# motor-board.net
KiCad netlist of a schematic drawn in EAGLE
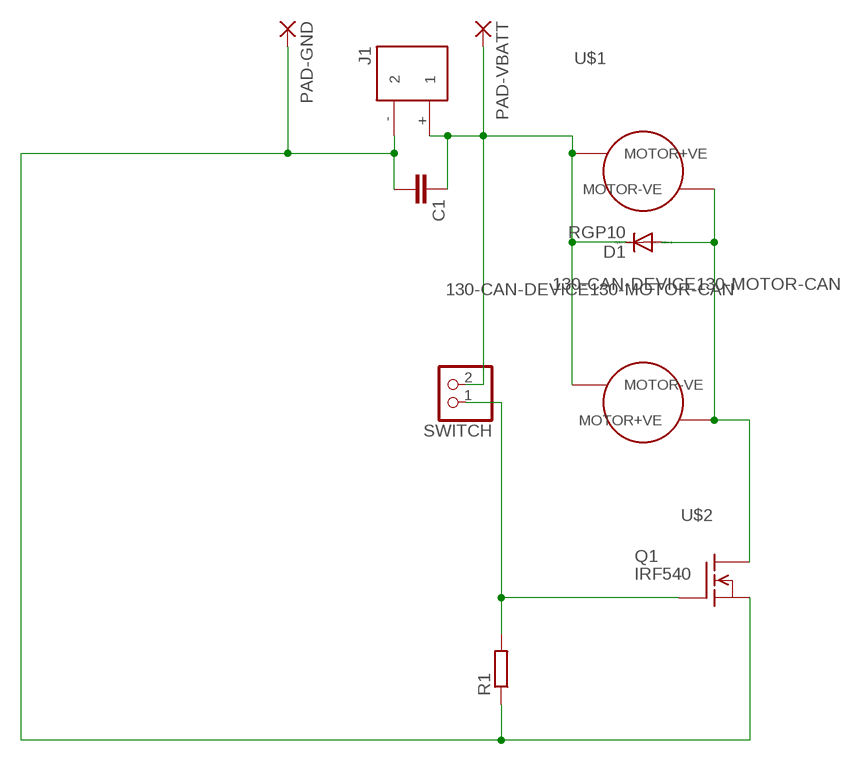
[diagram p0: schematic, sheet 1]

(export (version "E")
  (design (tool "Eeschema 10.0.6"))
  (components
    (comp (ref "C1")
      (value "C-EU050-024X044")
      (footprint "eagle-import:C050-024X044")
      (libsource (lib "eagle-import") (part "C-EU050-024X044"))
    )
    (comp (ref "D1")
      (value "RGP10")
      (footprint "eagle-import:DO41-10")
      (libsource (lib "eagle-import") (part "RGP10"))
    )
    (comp (ref "J1")
      (value "XT60_FEMALE")
      (footprint "eagle-import:XT60_FEMALE")
      (libsource (lib "eagle-import") (part "XT60_FEMALE"))
    )
    (comp (ref "PAD-GND")
      (value "WIREPAD3,81/1,4")
      (footprint "eagle-import:3,81_1,4")
      (libsource (lib "eagle-import") (part "WIREPAD3,81/1,4"))
    )
    (comp (ref "PAD-VBATT")
      (value "WIREPAD3,81/1,4")
      (footprint "eagle-import:3,81_1,4")
      (libsource (lib "eagle-import") (part "WIREPAD3,81/1,4"))
    )
    (comp (ref "Q1")
      (value "IRF540")
      (footprint "eagle-import:TO220")
      (libsource (lib "eagle-import") (part "IRF540"))
    )
    (comp (ref "R1")
      (value "R-EU_0309/10")
      (footprint "eagle-import:0309_10")
      (libsource (lib "eagle-import") (part "R-EU_0309/10"))
    )
    (comp (ref "SWITCH")
      (value "PINHD-1X2")
      (footprint "eagle-import:1X02")
      (libsource (lib "eagle-import") (part "PINHD-1X2"))
    )
    (comp (ref "U$1")
      (value "130-CAN-DEVICE130-MOTOR-CAN")
      (footprint "eagle-import:130-MOTOR-CAN")
      (libsource (lib "eagle-import") (part "130-CAN-DEVICE130-MOTOR-CAN"))
    )
    (comp (ref "U$2")
      (value "130-CAN-DEVICE130-MOTOR-CAN")
      (footprint "eagle-import:130-MOTOR-CAN")
      (libsource (lib "eagle-import") (part "130-CAN-DEVICE130-MOTOR-CAN"))
    )
  )
  (nets
    (net (code "1") (name "Net-(J1-1)") (class "Default")
      (node (ref "C1") (pin "1") (pinfunction "1_1") (pintype "passive"))
      (node (ref "D1") (pin "C") (pinfunction "C_C") (pintype "passive"))
      (node (ref "J1") (pin "+") (pinfunction "1_+") (pintype "bidirectional"))
      (node (ref "PAD-VBATT") (pin "1") (pinfunction "P_1") (pintype "passive"))
      (node (ref "SWITCH") (pin "2") (pinfunction "2_2") (pintype "passive"))
      (node (ref "U$1") (pin "MOTOR+VE") (pinfunction "MOTOR+VE_MOTOR+VE") (pintype "bidirectional"))
      (node (ref "U$2") (pin "MOTOR-VE") (pinfunction "MOTOR-VE_MOTOR-VE") (pintype "bidirectional"))
    )
    (net (code "2") (name "Net-(J1-2)") (class "Default")
      (node (ref "C1") (pin "2") (pinfunction "2_2") (pintype "passive"))
      (node (ref "J1") (pin "-") (pinfunction "2_-") (pintype "bidirectional"))
      (node (ref "PAD-GND") (pin "1") (pinfunction "P_1") (pintype "passive"))
      (node (ref "Q1") (pin "3") (pinfunction "S_3") (pintype "passive"))
      (node (ref "R1") (pin "1") (pinfunction "1_1") (pintype "passive"))
    )
    (net (code "3") (name "Net-(Q1-D)") (class "Default")
      (node (ref "D1") (pin "A") (pinfunction "A_A") (pintype "passive"))
      (node (ref "Q1") (pin "2") (pinfunction "D_2") (pintype "passive"))
      (node (ref "U$1") (pin "MOTOR-VE") (pinfunction "MOTOR-VE_MOTOR-VE") (pintype "bidirectional"))
      (node (ref "U$2") (pin "MOTOR+VE") (pinfunction "MOTOR+VE_MOTOR+VE") (pintype "bidirectional"))
    )
    (net (code "4") (name "Net-(Q1-G)") (class "Default")
      (node (ref "Q1") (pin "1") (pinfunction "G_1") (pintype "passive"))
      (node (ref "R1") (pin "2") (pinfunction "2_2") (pintype "passive"))
      (node (ref "SWITCH") (pin "1") (pinfunction "1_1") (pintype "passive"))
    )
  )
)
